# CLKB_analog_phase_detector.net
KiCad netlist of a schematic drawn in Altium Designer
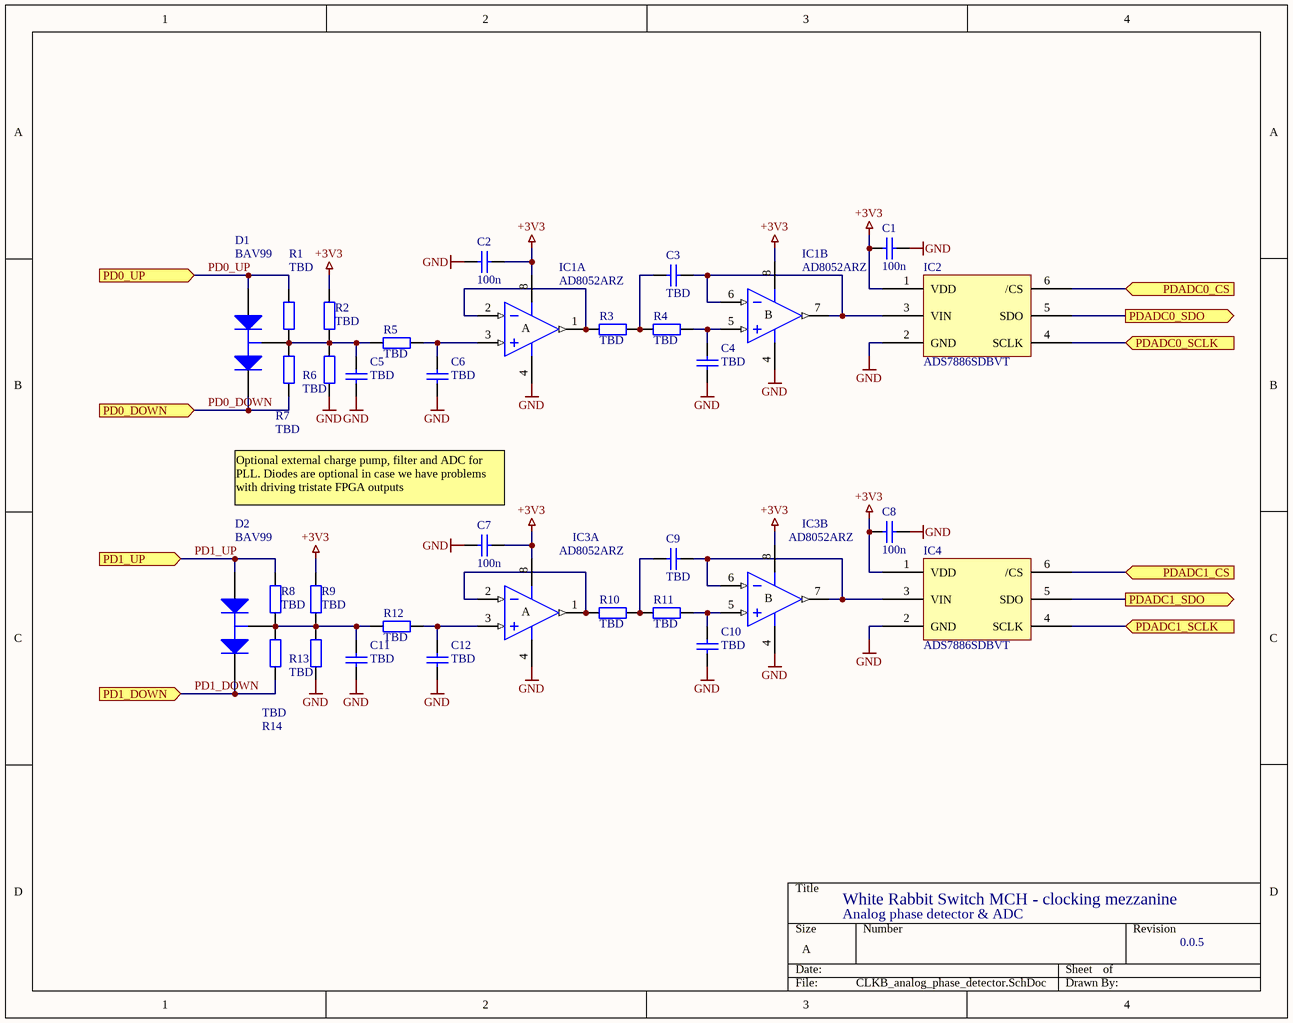
[diagram p0: CLKB_analog_phase_detector.SchDoc]

(export (version "E")
  (design (tool "Eeschema 10.0.6"))
  (components
    (comp (ref "C1")
      (value "100n")
      (footprint "CAPC1608X87N")
      (description "Capacitor")
      (fields (field (name "Comment") "Cap") (field (name "PUBLISHER") "Altium Limited"))
      (libsource (lib "Miscellaneous Devices") (part "Cap"))
    )
    (comp (ref "C2")
      (value "100n")
      (footprint "CAPC1608X87N")
      (description "Capacitor")
      (fields (field (name "Comment") "Cap") (field (name "PUBLISHER") "Altium Limited"))
      (libsource (lib "Miscellaneous Devices") (part "Cap"))
    )
    (comp (ref "C3")
      (value "TBD")
      (footprint "CAPC1608X87N")
      (description "Capacitor")
      (fields (field (name "Comment") "Cap") (field (name "PUBLISHER") "Altium Limited"))
      (libsource (lib "Miscellaneous Devices") (part "Cap"))
    )
    (comp (ref "C4")
      (value "TBD")
      (footprint "CAPC1608X87N")
      (description "Capacitor")
      (fields (field (name "Comment") "Cap") (field (name "PUBLISHER") "Altium Limited"))
      (libsource (lib "Miscellaneous Devices") (part "Cap"))
    )
    (comp (ref "C5")
      (value "TBD")
      (footprint "CAPC1608X87N")
      (description "Capacitor")
      (fields (field (name "Comment") "Cap") (field (name "PUBLISHER") "Altium Limited"))
      (libsource (lib "Miscellaneous Devices") (part "Cap"))
    )
    (comp (ref "C6")
      (value "TBD")
      (footprint "CAPC1608X87N")
      (description "Capacitor")
      (fields (field (name "Comment") "Cap") (field (name "PUBLISHER") "Altium Limited"))
      (libsource (lib "Miscellaneous Devices") (part "Cap"))
    )
    (comp (ref "C7")
      (value "100n")
      (footprint "CAPC1608X87N")
      (description "Capacitor")
      (fields (field (name "Comment") "Cap") (field (name "PUBLISHER") "Altium Limited"))
      (libsource (lib "Miscellaneous Devices") (part "Cap"))
    )
    (comp (ref "C8")
      (value "100n")
      (footprint "CC1608-0603")
      (description "Capacitor")
      (fields (field (name "Comment") "Cap") (field (name "PUBLISHER") "Altium Limited"))
      (libsource (lib "Miscellaneous Devices") (part "Cap"))
    )
    (comp (ref "C9")
      (value "TBD")
      (footprint "CAPC1608X87N")
      (description "Capacitor")
      (fields (field (name "Comment") "Cap") (field (name "PUBLISHER") "Altium Limited"))
      (libsource (lib "Miscellaneous Devices") (part "Cap"))
    )
    (comp (ref "C10")
      (value "TBD")
      (footprint "CAPC1608X87N")
      (description "Capacitor")
      (fields (field (name "Comment") "Cap") (field (name "PUBLISHER") "Altium Limited"))
      (libsource (lib "Miscellaneous Devices") (part "Cap"))
    )
    (comp (ref "C11")
      (value "TBD")
      (footprint "CAPC1608X87N")
      (description "Capacitor")
      (fields (field (name "Comment") "Cap") (field (name "PUBLISHER") "Altium Limited"))
      (libsource (lib "Miscellaneous Devices") (part "Cap"))
    )
    (comp (ref "C12")
      (value "TBD")
      (footprint "CAPC1608X87N")
      (description "Capacitor")
      (fields (field (name "Comment") "Cap") (field (name "PUBLISHER") "Altium Limited"))
      (libsource (lib "Miscellaneous Devices") (part "Cap"))
    )
    (comp (ref "D1")
      (value "BAV99")
      (footprint "SOT-23")
      (description "Silicon Switching Diode Array for High-Speed Switching")
      (fields (field (name "PUBLISHER") "Altium Limited"))
      (libsource (lib "Infineon Discrete Diode") (part "BAV99"))
    )
    (comp (ref "D2")
      (value "BAV99")
      (footprint "SOT-23")
      (description "Silicon Switching Diode Array for High-Speed Switching")
      (fields (field (name "PUBLISHER") "Altium Limited"))
      (libsource (lib "Infineon Discrete Diode") (part "BAV99"))
    )
    (comp (ref "IC1")
      (value "AD8052ARZ")
      (footprint "SOIC127P600-8AL")
      (description "Low Cost, High-Speed Rail-to-Rail Amplifier")
      (fields (field (name "Comment") "AD8052") (field (name "PUBLISHER") "Altium Limited"))
      (libsource (lib "wr_switch") (part "AD8052"))
    )
    (comp (ref "IC2")
      (value "ADS7886SDBVT")
      (footprint "SOT23A-6L")
      (description "TI 1 MSPS serial ADC")
      (fields (field (name "Comment") "ADS7886"))
      (libsource (lib "wr_switch") (part "ADS7886"))
    )
    (comp (ref "IC3")
      (value "AD8052ARZ")
      (footprint "SOIC127P600-8AL")
      (description "Low Cost, High-Speed Rail-to-Rail Amplifier")
      (fields (field (name "Comment") "AD8052") (field (name "PUBLISHER") "Altium Limited"))
      (libsource (lib "wr_switch") (part "AD8052"))
    )
    (comp (ref "IC4")
      (value "ADS7886SDBVT")
      (footprint "SOT23A-6L")
      (description "TI 1 MSPS serial ADC")
      (fields (field (name "Comment") "ADS7886"))
      (libsource (lib "wr_switch") (part "ADS7886"))
    )
    (comp (ref "R1")
      (value "TBD")
      (footprint "RESC1608X55N")
      (description "Resistor")
      (fields (field (name "Comment") "Res2") (field (name "PUBLISHER") "Altium Limited"))
      (libsource (lib "") (part "Res2_1"))
    )
    (comp (ref "R2")
      (value "TBD")
      (footprint "RESC1608X55N")
      (description "Resistor")
      (fields (field (name "Comment") "Res2") (field (name "PUBLISHER") "Altium Limited"))
      (libsource (lib "") (part "Res2_1"))
    )
    (comp (ref "R3")
      (value "TBD")
      (footprint "RESC1608X55N")
      (description "Resistor")
      (fields (field (name "Comment") "Res2") (field (name "PUBLISHER") "Altium Limited"))
      (libsource (lib "Miscellaneous Devices") (part "Res2"))
    )
    (comp (ref "R4")
      (value "TBD")
      (footprint "RESC1608X55N")
      (description "Resistor")
      (fields (field (name "Comment") "Res2") (field (name "PUBLISHER") "Altium Limited"))
      (libsource (lib "Miscellaneous Devices") (part "Res2"))
    )
    (comp (ref "R5")
      (value "TBD")
      (footprint "RESC1608X55N")
      (description "Resistor")
      (fields (field (name "Comment") "Res2") (field (name "PUBLISHER") "Altium Limited"))
      (libsource (lib "Miscellaneous Devices") (part "Res2"))
    )
    (comp (ref "R6")
      (value "TBD")
      (footprint "RESC1608X55N")
      (description "Resistor")
      (fields (field (name "Comment") "Res2") (field (name "PUBLISHER") "Altium Limited"))
      (libsource (lib "") (part "Res2_1"))
    )
    (comp (ref "R7")
      (value "TBD")
      (footprint "RESC1608X55N")
      (description "Resistor")
      (fields (field (name "Comment") "Res2") (field (name "PUBLISHER") "Altium Limited"))
      (libsource (lib "") (part "Res2_1"))
    )
    (comp (ref "R8")
      (value "TBD")
      (footprint "RESC1608X55N")
      (description "Resistor")
      (fields (field (name "Comment") "Res2") (field (name "PUBLISHER") "Altium Limited"))
      (libsource (lib "") (part "Res2_1"))
    )
    (comp (ref "R9")
      (value "TBD")
      (footprint "RESC1608X55N")
      (description "Resistor")
      (fields (field (name "Comment") "Res2") (field (name "PUBLISHER") "Altium Limited"))
      (libsource (lib "") (part "Res2_1"))
    )
    (comp (ref "R10")
      (value "TBD")
      (footprint "RESC1608X55N")
      (description "Resistor")
      (fields (field (name "Comment") "Res2") (field (name "PUBLISHER") "Altium Limited"))
      (libsource (lib "Miscellaneous Devices") (part "Res2"))
    )
    (comp (ref "R11")
      (value "TBD")
      (footprint "RESC1608X55N")
      (description "Resistor")
      (fields (field (name "Comment") "Res2") (field (name "PUBLISHER") "Altium Limited"))
      (libsource (lib "Miscellaneous Devices") (part "Res2"))
    )
    (comp (ref "R12")
      (value "TBD")
      (footprint "RESC1608X55N")
      (description "Resistor")
      (fields (field (name "Comment") "Res2") (field (name "PUBLISHER") "Altium Limited"))
      (libsource (lib "Miscellaneous Devices") (part "Res2"))
    )
    (comp (ref "R13")
      (value "TBD")
      (footprint "RESC1608X55N")
      (description "Resistor")
      (fields (field (name "Comment") "Res2") (field (name "PUBLISHER") "Altium Limited"))
      (libsource (lib "") (part "Res2_1"))
    )
    (comp (ref "R14")
      (value "TBD")
      (footprint "RESC1608X55N")
      (description "Resistor")
      (fields (field (name "Comment") "Res2") (field (name "PUBLISHER") "Altium Limited"))
      (libsource (lib "") (part "Res2_1"))
    )
  )
  (nets
    (net (code "1") (name "+3V3") (class "Default")
      (node (ref "C1") (pin "1") (pinfunction "1_1") (pintype "passive"))
      (node (ref "C2") (pin "1") (pinfunction "1_1") (pintype "passive"))
      (node (ref "C7") (pin "1") (pinfunction "1_1") (pintype "passive"))
      (node (ref "C8") (pin "1") (pinfunction "1_1") (pintype "passive"))
      (node (ref "IC1") (pin "8") (pinfunction "V+_8") (pintype "power_in"))
      (node (ref "IC2") (pin "1") (pinfunction "VDD_1") (pintype "passive"))
      (node (ref "IC3") (pin "8") (pinfunction "V+_8") (pintype "power_in"))
      (node (ref "IC4") (pin "1") (pinfunction "VDD_1") (pintype "passive"))
      (node (ref "R2") (pin "2") (pinfunction "2_2") (pintype "passive"))
      (node (ref "R9") (pin "2") (pinfunction "2_2") (pintype "passive"))
    )
    (net (code "2") (name "/PD0_DOWN") (class "Default")
      (node (ref "D1") (pin "2") (pinfunction "K_2") (pintype "passive"))
      (node (ref "R7") (pin "1") (pinfunction "1_1") (pintype "passive"))
    )
    (net (code "3") (name "/PD0_UP") (class "Default")
      (node (ref "D1") (pin "1") (pinfunction "A_1") (pintype "passive"))
      (node (ref "R1") (pin "2") (pinfunction "2_2") (pintype "passive"))
    )
    (net (code "4") (name "/PD1_DOWN") (class "Default")
      (node (ref "D2") (pin "2") (pinfunction "K_2") (pintype "passive"))
      (node (ref "R14") (pin "1") (pinfunction "1_1") (pintype "passive"))
    )
    (net (code "5") (name "/PD1_UP") (class "Default")
      (node (ref "D2") (pin "1") (pinfunction "A_1") (pintype "passive"))
      (node (ref "R8") (pin "2") (pinfunction "2_2") (pintype "passive"))
    )
    (net (code "6") (name "/PDADC0_CS") (class "Default")
      (node (ref "IC2") (pin "6") (pinfunction "/CS_6") (pintype "passive"))
    )
    (net (code "7") (name "/PDADC0_SCLK") (class "Default")
      (node (ref "IC2") (pin "4") (pinfunction "SCLK_4") (pintype "passive"))
    )
    (net (code "8") (name "/PDADC0_SDO") (class "Default")
      (node (ref "IC2") (pin "5") (pinfunction "SDO_5") (pintype "passive"))
    )
    (net (code "9") (name "/PDADC1_CS") (class "Default")
      (node (ref "IC4") (pin "6") (pinfunction "/CS_6") (pintype "passive"))
    )
    (net (code "10") (name "/PDADC1_SCLK") (class "Default")
      (node (ref "IC4") (pin "4") (pinfunction "SCLK_4") (pintype "passive"))
    )
    (net (code "11") (name "/PDADC1_SDO") (class "Default")
      (node (ref "IC4") (pin "5") (pinfunction "SDO_5") (pintype "passive"))
    )
    (net (code "12") (name "GND") (class "Default")
      (node (ref "C1") (pin "2") (pinfunction "2_2") (pintype "passive"))
      (node (ref "C10") (pin "1") (pinfunction "1_1") (pintype "passive"))
      (node (ref "C11") (pin "1") (pinfunction "1_1") (pintype "passive"))
      (node (ref "C12") (pin "1") (pinfunction "1_1") (pintype "passive"))
      (node (ref "C2") (pin "2") (pinfunction "2_2") (pintype "passive"))
      (node (ref "C4") (pin "1") (pinfunction "1_1") (pintype "passive"))
      (node (ref "C5") (pin "1") (pinfunction "1_1") (pintype "passive"))
      (node (ref "C6") (pin "1") (pinfunction "1_1") (pintype "passive"))
      (node (ref "C7") (pin "2") (pinfunction "2_2") (pintype "passive"))
      (node (ref "C8") (pin "2") (pinfunction "2_2") (pintype "passive"))
      (node (ref "IC1") (pin "4") (pinfunction "V-_4") (pintype "power_in"))
      (node (ref "IC2") (pin "2") (pinfunction "GND_2") (pintype "passive"))
      (node (ref "IC3") (pin "4") (pinfunction "V-_4") (pintype "power_in"))
      (node (ref "IC4") (pin "2") (pinfunction "GND_2") (pintype "passive"))
      (node (ref "R13") (pin "1") (pinfunction "1_1") (pintype "passive"))
      (node (ref "R6") (pin "1") (pinfunction "1_1") (pintype "passive"))
    )
    (net (code "13") (name "Net-(C3-Pad2)") (class "Default")
      (node (ref "C3") (pin "2") (pinfunction "2_2") (pintype "passive"))
      (node (ref "R3") (pin "2") (pinfunction "2_2") (pintype "passive"))
      (node (ref "R4") (pin "1") (pinfunction "1_1") (pintype "passive"))
    )
    (net (code "14") (name "Net-(C9-Pad2)") (class "Default")
      (node (ref "C9") (pin "2") (pinfunction "2_2") (pintype "passive"))
      (node (ref "R10") (pin "2") (pinfunction "2_2") (pintype "passive"))
      (node (ref "R11") (pin "1") (pinfunction "1_1") (pintype "passive"))
    )
    (net (code "15") (name "Net-(D1-C)") (class "Default")
      (node (ref "C5") (pin "2") (pinfunction "2_2") (pintype "passive"))
      (node (ref "D1") (pin "3") (pinfunction "C_3") (pintype "passive"))
      (node (ref "R1") (pin "1") (pinfunction "1_1") (pintype "passive"))
      (node (ref "R2") (pin "1") (pinfunction "1_1") (pintype "passive"))
      (node (ref "R5") (pin "1") (pinfunction "1_1") (pintype "passive"))
      (node (ref "R6") (pin "2") (pinfunction "2_2") (pintype "passive"))
      (node (ref "R7") (pin "2") (pinfunction "2_2") (pintype "passive"))
    )
    (net (code "16") (name "Net-(D2-C)") (class "Default")
      (node (ref "C11") (pin "2") (pinfunction "2_2") (pintype "passive"))
      (node (ref "D2") (pin "3") (pinfunction "C_3") (pintype "passive"))
      (node (ref "R12") (pin "1") (pinfunction "1_1") (pintype "passive"))
      (node (ref "R13") (pin "2") (pinfunction "2_2") (pintype "passive"))
      (node (ref "R14") (pin "2") (pinfunction "2_2") (pintype "passive"))
      (node (ref "R8") (pin "1") (pinfunction "1_1") (pintype "passive"))
      (node (ref "R9") (pin "1") (pinfunction "1_1") (pintype "passive"))
    )
    (net (code "17") (name "Net-(IC1A-IN+)") (class "Default")
      (node (ref "C6") (pin "2") (pinfunction "2_2") (pintype "passive"))
      (node (ref "IC1") (pin "3") (pinfunction "IN+_3") (pintype "input"))
      (node (ref "R5") (pin "2") (pinfunction "2_2") (pintype "passive"))
    )
    (net (code "18") (name "Net-(IC1A-IN-)") (class "Default")
      (node (ref "IC1") (pin "1") (pinfunction "OUT_1") (pintype "output"))
      (node (ref "IC1") (pin "2") (pinfunction "IN-_2") (pintype "input"))
      (node (ref "R3") (pin "1") (pinfunction "1_1") (pintype "passive"))
    )
    (net (code "19") (name "Net-(IC1B-IN+)") (class "Default")
      (node (ref "C4") (pin "2") (pinfunction "2_2") (pintype "passive"))
      (node (ref "IC1") (pin "5") (pinfunction "IN+_5") (pintype "input"))
      (node (ref "R4") (pin "2") (pinfunction "2_2") (pintype "passive"))
    )
    (net (code "20") (name "Net-(IC1B-IN-)") (class "Default")
      (node (ref "C3") (pin "1") (pinfunction "1_1") (pintype "passive"))
      (node (ref "IC1") (pin "6") (pinfunction "IN-_6") (pintype "input"))
      (node (ref "IC1") (pin "7") (pinfunction "OUT_7") (pintype "output"))
      (node (ref "IC2") (pin "3") (pinfunction "VIN_3") (pintype "passive"))
    )
    (net (code "21") (name "Net-(IC3A-IN+)") (class "Default")
      (node (ref "C12") (pin "2") (pinfunction "2_2") (pintype "passive"))
      (node (ref "IC3") (pin "3") (pinfunction "IN+_3") (pintype "input"))
      (node (ref "R12") (pin "2") (pinfunction "2_2") (pintype "passive"))
    )
    (net (code "22") (name "Net-(IC3A-IN-)") (class "Default")
      (node (ref "IC3") (pin "1") (pinfunction "OUT_1") (pintype "output"))
      (node (ref "IC3") (pin "2") (pinfunction "IN-_2") (pintype "input"))
      (node (ref "R10") (pin "1") (pinfunction "1_1") (pintype "passive"))
    )
    (net (code "23") (name "Net-(IC3B-IN+)") (class "Default")
      (node (ref "C10") (pin "2") (pinfunction "2_2") (pintype "passive"))
      (node (ref "IC3") (pin "5") (pinfunction "IN+_5") (pintype "input"))
      (node (ref "R11") (pin "2") (pinfunction "2_2") (pintype "passive"))
    )
    (net (code "24") (name "Net-(IC3B-IN-)") (class "Default")
      (node (ref "C9") (pin "1") (pinfunction "1_1") (pintype "passive"))
      (node (ref "IC3") (pin "6") (pinfunction "IN-_6") (pintype "input"))
      (node (ref "IC3") (pin "7") (pinfunction "OUT_7") (pintype "output"))
      (node (ref "IC4") (pin "3") (pinfunction "VIN_3") (pintype "passive"))
    )
  )
)
